# LINX_DMX_RECIEVER.net
KiCad netlist of a schematic drawn in EAGLE
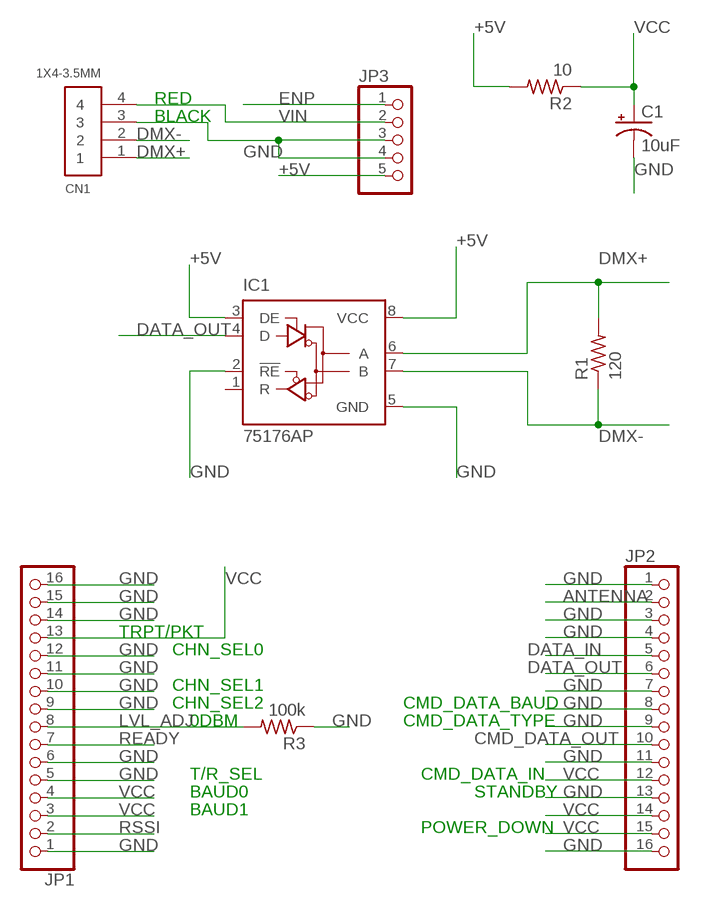
[diagram p0: schematic, sheet 1]

(export (version "E")
  (design (tool "Eeschema 10.0.6"))
  (components
    (comp (ref "C1")
      (value "10uF")
      (footprint "eagle-import:B45181A")
      (libsource (lib "eagle-import") (part "CPOL-USB45181A"))
    )
    (comp (ref "CN1")
      (value "1X4-3.5MM")
      (footprint "eagle-import:1X04-3.5MM")
      (libsource (lib "eagle-import") (part "1X4-3.5MM"))
    )
    (comp (ref "IC1")
      (value "75176AP")
      (footprint "eagle-import:DIL08")
      (libsource (lib "eagle-import") (part "75176AP"))
    )
    (comp (ref "JP1")
      (value "PINHD-1X16")
      (footprint "eagle-import:1X16")
      (libsource (lib "eagle-import") (part "PINHD-1X16"))
    )
    (comp (ref "JP2")
      (value "PINHD-1X16")
      (footprint "eagle-import:1X16")
      (libsource (lib "eagle-import") (part "PINHD-1X16"))
    )
    (comp (ref "JP3")
      (value "PINHD-1X5/90")
      (footprint "eagle-import:1X05_90")
      (libsource (lib "eagle-import") (part "PINHD-1X5/90"))
    )
    (comp (ref "R1")
      (value "120")
      (footprint "eagle-import:0414_15")
      (libsource (lib "eagle-import") (part "R-US_0414/15"))
    )
    (comp (ref "R2")
      (value "10")
      (footprint "eagle-import:0414_15")
      (libsource (lib "eagle-import") (part "R-US_0414/15"))
    )
    (comp (ref "R3")
      (value "100k")
      (footprint "eagle-import:0414_15")
      (libsource (lib "eagle-import") (part "R-US_0414/15"))
    )
  )
  (nets
    (net (code "1") (name "/+5V") (class "Default")
      (node (ref "IC1") (pin "3") (pinfunction "DE_3") (pintype "input"))
      (node (ref "IC1") (pin "8") (pinfunction "VCC_8") (pintype "power_in"))
      (node (ref "JP3") (pin "5") (pinfunction "5_5") (pintype "passive"))
      (node (ref "R2") (pin "2") (pinfunction "2_2") (pintype "passive"))
    )
    (net (code "2") (name "/ANTENNA") (class "Default")
      (node (ref "JP2") (pin "2") (pinfunction "2_2") (pintype "passive"))
    )
    (net (code "3") (name "/CMD_DATA_OUT") (class "Default")
      (node (ref "JP2") (pin "10") (pinfunction "10_10") (pintype "passive"))
    )
    (net (code "4") (name "/DATA_IN") (class "Default")
      (node (ref "JP2") (pin "5") (pinfunction "5_5") (pintype "passive"))
    )
    (net (code "5") (name "/DATA_OUT") (class "Default")
      (node (ref "IC1") (pin "4") (pinfunction "D_4") (pintype "input"))
      (node (ref "JP2") (pin "6") (pinfunction "6_6") (pintype "passive"))
    )
    (net (code "6") (name "/DMX+") (class "Default")
      (node (ref "CN1") (pin "1") (pinfunction "1_1") (pintype "bidirectional"))
      (node (ref "IC1") (pin "6") (pinfunction "A_6") (pintype "output"))
      (node (ref "R1") (pin "2") (pinfunction "2_2") (pintype "passive"))
    )
    (net (code "7") (name "/DMX-") (class "Default")
      (node (ref "CN1") (pin "2") (pinfunction "2_2") (pintype "bidirectional"))
      (node (ref "IC1") (pin "7") (pinfunction "B_7") (pintype "output"))
      (node (ref "R1") (pin "1") (pinfunction "1_1") (pintype "passive"))
    )
    (net (code "8") (name "/ENP") (class "Default")
      (node (ref "JP3") (pin "1") (pinfunction "1_1") (pintype "passive"))
    )
    (net (code "9") (name "/GND") (class "Default")
      (node (ref "C1") (pin "-") (pinfunction "-_-") (pintype "passive"))
      (node (ref "CN1") (pin "3") (pinfunction "3_3") (pintype "bidirectional"))
      (node (ref "IC1") (pin "2") (pinfunction "~{RE}_2") (pintype "input"))
      (node (ref "IC1") (pin "5") (pinfunction "GND_5") (pintype "power_in"))
      (node (ref "JP1") (pin "1") (pinfunction "1_1") (pintype "passive"))
      (node (ref "JP1") (pin "10") (pinfunction "10_10") (pintype "passive"))
      (node (ref "JP1") (pin "11") (pinfunction "11_11") (pintype "passive"))
      (node (ref "JP1") (pin "12") (pinfunction "12_12") (pintype "passive"))
      (node (ref "JP1") (pin "14") (pinfunction "14_14") (pintype "passive"))
      (node (ref "JP1") (pin "15") (pinfunction "15_15") (pintype "passive"))
      (node (ref "JP1") (pin "16") (pinfunction "16_16") (pintype "passive"))
      (node (ref "JP1") (pin "5") (pinfunction "5_5") (pintype "passive"))
      (node (ref "JP1") (pin "6") (pinfunction "6_6") (pintype "passive"))
      (node (ref "JP1") (pin "9") (pinfunction "9_9") (pintype "passive"))
      (node (ref "JP2") (pin "1") (pinfunction "1_1") (pintype "passive"))
      (node (ref "JP2") (pin "11") (pinfunction "11_11") (pintype "passive"))
      (node (ref "JP2") (pin "13") (pinfunction "13_13") (pintype "passive"))
      (node (ref "JP2") (pin "16") (pinfunction "16_16") (pintype "passive"))
      (node (ref "JP2") (pin "3") (pinfunction "3_3") (pintype "passive"))
      (node (ref "JP2") (pin "4") (pinfunction "4_4") (pintype "passive"))
      (node (ref "JP2") (pin "7") (pinfunction "7_7") (pintype "passive"))
      (node (ref "JP2") (pin "8") (pinfunction "8_8") (pintype "passive"))
      (node (ref "JP2") (pin "9") (pinfunction "9_9") (pintype "passive"))
      (node (ref "JP3") (pin "3") (pinfunction "3_3") (pintype "passive"))
      (node (ref "JP3") (pin "4") (pinfunction "4_4") (pintype "passive"))
      (node (ref "R3") (pin "1") (pinfunction "1_1") (pintype "passive"))
    )
    (net (code "10") (name "/LVL_ADJ") (class "Default")
      (node (ref "JP1") (pin "8") (pinfunction "8_8") (pintype "passive"))
      (node (ref "R3") (pin "2") (pinfunction "2_2") (pintype "passive"))
    )
    (net (code "11") (name "/READY") (class "Default")
      (node (ref "JP1") (pin "7") (pinfunction "7_7") (pintype "passive"))
    )
    (net (code "12") (name "/RSSI") (class "Default")
      (node (ref "JP1") (pin "2") (pinfunction "2_2") (pintype "passive"))
    )
    (net (code "13") (name "/VCC") (class "Default")
      (node (ref "C1") (pin "+") (pinfunction "+_+") (pintype "passive"))
      (node (ref "JP1") (pin "13") (pinfunction "13_13") (pintype "passive"))
      (node (ref "JP1") (pin "3") (pinfunction "3_3") (pintype "passive"))
      (node (ref "JP1") (pin "4") (pinfunction "4_4") (pintype "passive"))
      (node (ref "JP2") (pin "12") (pinfunction "12_12") (pintype "passive"))
      (node (ref "JP2") (pin "14") (pinfunction "14_14") (pintype "passive"))
      (node (ref "JP2") (pin "15") (pinfunction "15_15") (pintype "passive"))
      (node (ref "R2") (pin "1") (pinfunction "1_1") (pintype "passive"))
    )
    (net (code "14") (name "/VIN") (class "Default")
      (node (ref "CN1") (pin "4") (pinfunction "4_4") (pintype "bidirectional"))
      (node (ref "JP3") (pin "2") (pinfunction "2_2") (pintype "passive"))
    )
    (net (code "15") (name "unconnected-(IC1-R-Pad1)") (class "Default")
      (node (ref "IC1") (pin "1") (pinfunction "R_1") (pintype "input"))
    )
  )
)
